# slice.net
KiCad netlist of a schematic drawn in EAGLE
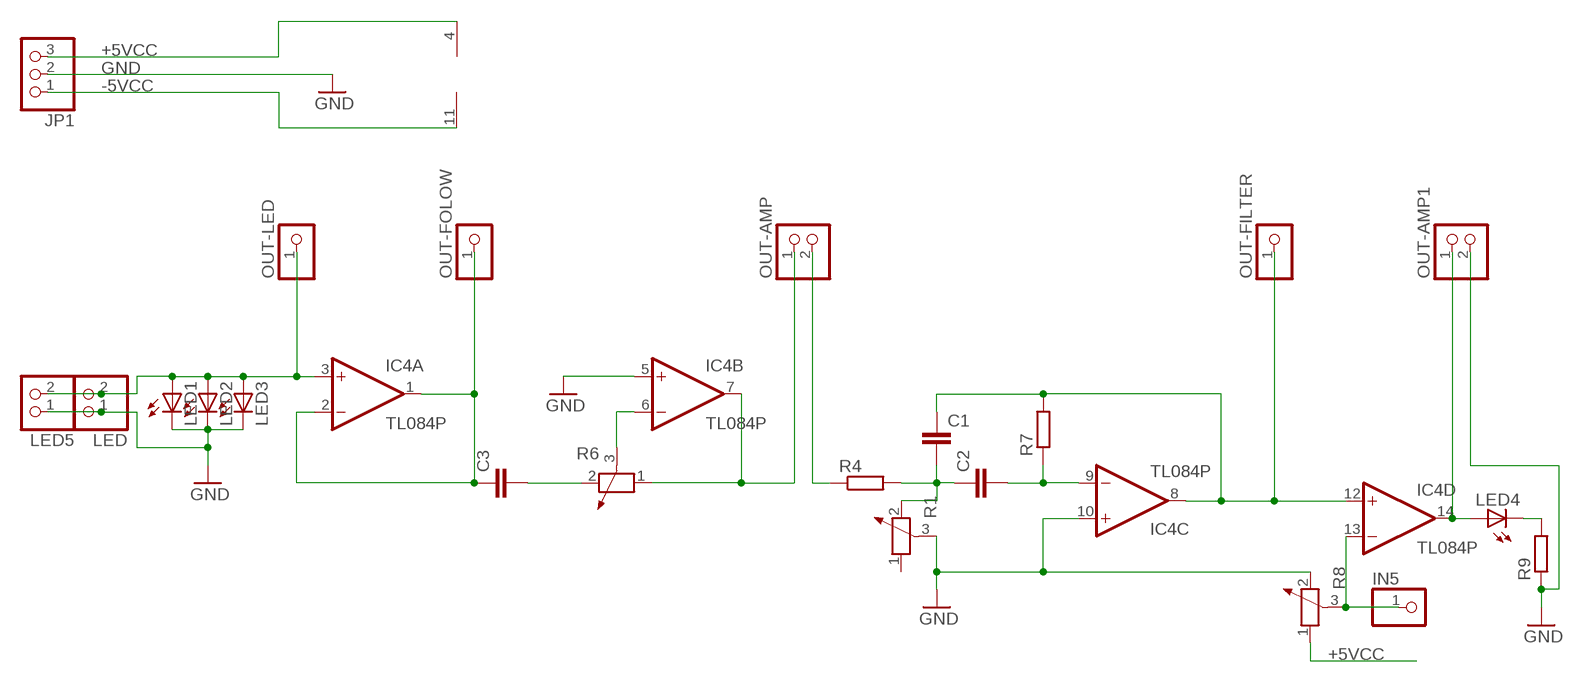
[diagram p0: schematic, sheet 1]

(export (version "E")
  (design (tool "Eeschema 10.0.6"))
  (components
    (comp (ref "C1")
      (value "C-EU150-064X183")
      (footprint "eagle-import:C150-064X183")
      (libsource (lib "eagle-import") (part "C-EU150-064X183"))
    )
    (comp (ref "C2")
      (value "C-EU150-064X183")
      (footprint "eagle-import:C150-064X183")
      (libsource (lib "eagle-import") (part "C-EU150-064X183"))
    )
    (comp (ref "C3")
      (value "C-EU050-024X044")
      (footprint "eagle-import:C050-024X044")
      (libsource (lib "eagle-import") (part "C-EU050-024X044"))
    )
    (comp (ref "IC4")
      (value "TL084P")
      (footprint "eagle-import:DIL14")
      (libsource (lib "eagle-import") (part "TL084P"))
    )
    (comp (ref "IN5")
      (value "PINHD-1X1")
      (footprint "eagle-import:1X01")
      (libsource (lib "eagle-import") (part "PINHD-1X1"))
    )
    (comp (ref "JP1")
      (value "PINHD-1X3")
      (footprint "eagle-import:1X03")
      (libsource (lib "eagle-import") (part "PINHD-1X3"))
    )
    (comp (ref "LED")
      (value "PINHD-1X2")
      (footprint "eagle-import:1X02")
      (libsource (lib "eagle-import") (part "PINHD-1X2"))
    )
    (comp (ref "LED1")
      (value "LED5MM")
      (footprint "eagle-import:LED5MM")
      (libsource (lib "eagle-import") (part "LED5MM"))
    )
    (comp (ref "LED2")
      (value "LED5MM")
      (footprint "eagle-import:LED5MM")
      (libsource (lib "eagle-import") (part "LED5MM"))
    )
    (comp (ref "LED3")
      (value "LED5MM")
      (footprint "eagle-import:LED5MM")
      (libsource (lib "eagle-import") (part "LED5MM"))
    )
    (comp (ref "LED4")
      (value "LED5MM")
      (footprint "eagle-import:LED5MM")
      (libsource (lib "eagle-import") (part "LED5MM"))
    )
    (comp (ref "LED5")
      (value "PINHD-1X2")
      (footprint "eagle-import:1X02")
      (libsource (lib "eagle-import") (part "PINHD-1X2"))
    )
    (comp (ref "OUT-AMP")
      (value "PINHD-1X2")
      (footprint "eagle-import:1X02")
      (libsource (lib "eagle-import") (part "PINHD-1X2"))
    )
    (comp (ref "OUT-AMP1")
      (value "PINHD-1X2")
      (footprint "eagle-import:1X02")
      (libsource (lib "eagle-import") (part "PINHD-1X2"))
    )
    (comp (ref "OUT-FILTER")
      (value "PINHD-1X1")
      (footprint "eagle-import:1X01")
      (libsource (lib "eagle-import") (part "PINHD-1X1"))
    )
    (comp (ref "OUT-FOLOW")
      (value "PINHD-1X1")
      (footprint "eagle-import:1X01")
      (libsource (lib "eagle-import") (part "PINHD-1X1"))
    )
    (comp (ref "OUT-LED")
      (value "PINHD-1X1")
      (footprint "eagle-import:1X01")
      (libsource (lib "eagle-import") (part "PINHD-1X1"))
    )
    (comp (ref "R1")
      (value "POTENTIOMETER_PT-10")
      (footprint "eagle-import:PT-10")
      (libsource (lib "eagle-import") (part "POTENTIOMETER_PT-10"))
    )
    (comp (ref "R4")
      (value "R-EU_0204/7")
      (footprint "eagle-import:0204_7")
      (libsource (lib "eagle-import") (part "R-EU_0204/7"))
    )
    (comp (ref "R6")
      (value "POTENTIOMETER_PT-10")
      (footprint "eagle-import:PT-10")
      (libsource (lib "eagle-import") (part "POTENTIOMETER_PT-10"))
    )
    (comp (ref "R7")
      (value "R-EU_0204/7")
      (footprint "eagle-import:0204_7")
      (libsource (lib "eagle-import") (part "R-EU_0204/7"))
    )
    (comp (ref "R8")
      (value "POTENTIOMETER_PT-10")
      (footprint "eagle-import:PT-10")
      (libsource (lib "eagle-import") (part "POTENTIOMETER_PT-10"))
    )
    (comp (ref "R9")
      (value "R-EU_0204/7")
      (footprint "eagle-import:0204_7")
      (libsource (lib "eagle-import") (part "R-EU_0204/7"))
    )
  )
  (nets
    (net (code "1") (name "/+5VCC") (class "Default")
      (node (ref "IC4") (pin "4") (pinfunction "V+_4") (pintype "power_in"))
      (node (ref "JP1") (pin "3") (pinfunction "3_3") (pintype "passive"))
      (node (ref "R8") (pin "1") (pinfunction "1_1") (pintype "passive"))
    )
    (net (code "2") (name "/-5VCC") (class "Default")
      (node (ref "IC4") (pin "11") (pinfunction "V-_11") (pintype "power_in"))
      (node (ref "JP1") (pin "1") (pinfunction "1_1") (pintype "passive"))
    )
    (net (code "3") (name "GND") (class "Default")
      (node (ref "IC4") (pin "10") (pinfunction "+IN_10") (pintype "input"))
      (node (ref "IC4") (pin "5") (pinfunction "+IN_5") (pintype "input"))
      (node (ref "JP1") (pin "2") (pinfunction "2_2") (pintype "passive"))
      (node (ref "LED") (pin "1") (pinfunction "1_1") (pintype "passive"))
      (node (ref "LED1") (pin "K") (pinfunction "C_K") (pintype "passive"))
      (node (ref "LED2") (pin "K") (pinfunction "C_K") (pintype "passive"))
      (node (ref "LED3") (pin "K") (pinfunction "C_K") (pintype "passive"))
      (node (ref "LED5") (pin "1") (pinfunction "1_1") (pintype "passive"))
      (node (ref "OUT-AMP1") (pin "2") (pinfunction "2_2") (pintype "passive"))
      (node (ref "R1") (pin "3") (pinfunction "3_3") (pintype "passive"))
      (node (ref "R8") (pin "2") (pinfunction "2_2") (pintype "passive"))
      (node (ref "R9") (pin "1") (pinfunction "1_1") (pintype "passive"))
    )
    (net (code "4") (name "Net-(C1-Pad2)") (class "Default")
      (node (ref "C1") (pin "2") (pinfunction "2_2") (pintype "passive"))
      (node (ref "C2") (pin "1") (pinfunction "1_1") (pintype "passive"))
      (node (ref "R1") (pin "2") (pinfunction "2_2") (pintype "passive"))
      (node (ref "R4") (pin "2") (pinfunction "2_2") (pintype "passive"))
    )
    (net (code "5") (name "Net-(C3-Pad2)") (class "Default")
      (node (ref "C3") (pin "2") (pinfunction "2_2") (pintype "passive"))
      (node (ref "R6") (pin "2") (pinfunction "2_2") (pintype "passive"))
    )
    (net (code "6") (name "Net-(IC4A-+IN)") (class "Default")
      (node (ref "IC4") (pin "3") (pinfunction "+IN_3") (pintype "input"))
      (node (ref "LED") (pin "2") (pinfunction "2_2") (pintype "passive"))
      (node (ref "LED1") (pin "A") (pinfunction "A_A") (pintype "passive"))
      (node (ref "LED2") (pin "A") (pinfunction "A_A") (pintype "passive"))
      (node (ref "LED3") (pin "A") (pinfunction "A_A") (pintype "passive"))
      (node (ref "LED5") (pin "2") (pinfunction "2_2") (pintype "passive"))
      (node (ref "OUT-LED") (pin "1") (pinfunction "1_1") (pintype "passive"))
    )
    (net (code "7") (name "Net-(IC4A--IN)") (class "Default")
      (node (ref "C3") (pin "1") (pinfunction "1_1") (pintype "passive"))
      (node (ref "IC4") (pin "1") (pinfunction "OUT_1") (pintype "output"))
      (node (ref "IC4") (pin "2") (pinfunction "-IN_2") (pintype "input"))
      (node (ref "OUT-FOLOW") (pin "1") (pinfunction "1_1") (pintype "passive"))
    )
    (net (code "8") (name "Net-(IC4B--IN)") (class "Default")
      (node (ref "IC4") (pin "6") (pinfunction "-IN_6") (pintype "input"))
      (node (ref "R6") (pin "3") (pinfunction "3_3") (pintype "passive"))
    )
    (net (code "9") (name "Net-(IC4B-OUT)") (class "Default")
      (node (ref "IC4") (pin "7") (pinfunction "OUT_7") (pintype "output"))
      (node (ref "OUT-AMP") (pin "1") (pinfunction "1_1") (pintype "passive"))
      (node (ref "R6") (pin "1") (pinfunction "1_1") (pintype "passive"))
    )
    (net (code "10") (name "Net-(IC4C--IN)") (class "Default")
      (node (ref "C2") (pin "2") (pinfunction "2_2") (pintype "passive"))
      (node (ref "IC4") (pin "9") (pinfunction "-IN_9") (pintype "input"))
      (node (ref "R7") (pin "1") (pinfunction "1_1") (pintype "passive"))
    )
    (net (code "11") (name "Net-(IC4C-OUT)") (class "Default")
      (node (ref "C1") (pin "1") (pinfunction "1_1") (pintype "passive"))
      (node (ref "IC4") (pin "12") (pinfunction "+IN_12") (pintype "input"))
      (node (ref "IC4") (pin "8") (pinfunction "OUT_8") (pintype "output"))
      (node (ref "OUT-FILTER") (pin "1") (pinfunction "1_1") (pintype "passive"))
      (node (ref "R7") (pin "2") (pinfunction "2_2") (pintype "passive"))
    )
    (net (code "12") (name "Net-(IC4D--IN)") (class "Default")
      (node (ref "IC4") (pin "13") (pinfunction "-IN_13") (pintype "input"))
      (node (ref "IN5") (pin "1") (pinfunction "1_1") (pintype "passive"))
      (node (ref "R8") (pin "3") (pinfunction "3_3") (pintype "passive"))
    )
    (net (code "13") (name "Net-(IC4D-OUT)") (class "Default")
      (node (ref "IC4") (pin "14") (pinfunction "OUT_14") (pintype "output"))
      (node (ref "LED4") (pin "A") (pinfunction "A_A") (pintype "passive"))
      (node (ref "OUT-AMP1") (pin "1") (pinfunction "1_1") (pintype "passive"))
    )
    (net (code "14") (name "Net-(LED4-C)") (class "Default")
      (node (ref "LED4") (pin "K") (pinfunction "C_K") (pintype "passive"))
      (node (ref "R9") (pin "2") (pinfunction "2_2") (pintype "passive"))
    )
    (net (code "15") (name "Net-(OUT-AMP-Pad2)") (class "Default")
      (node (ref "OUT-AMP") (pin "2") (pinfunction "2_2") (pintype "passive"))
      (node (ref "R4") (pin "1") (pinfunction "1_1") (pintype "passive"))
    )
    (net (code "16") (name "unconnected-(R1-Pad1)") (class "Default")
      (node (ref "R1") (pin "1") (pinfunction "1_1") (pintype "passive"))
    )
  )
)
